# 4.net
KiCad netlist of a schematic drawn in Altium Designer
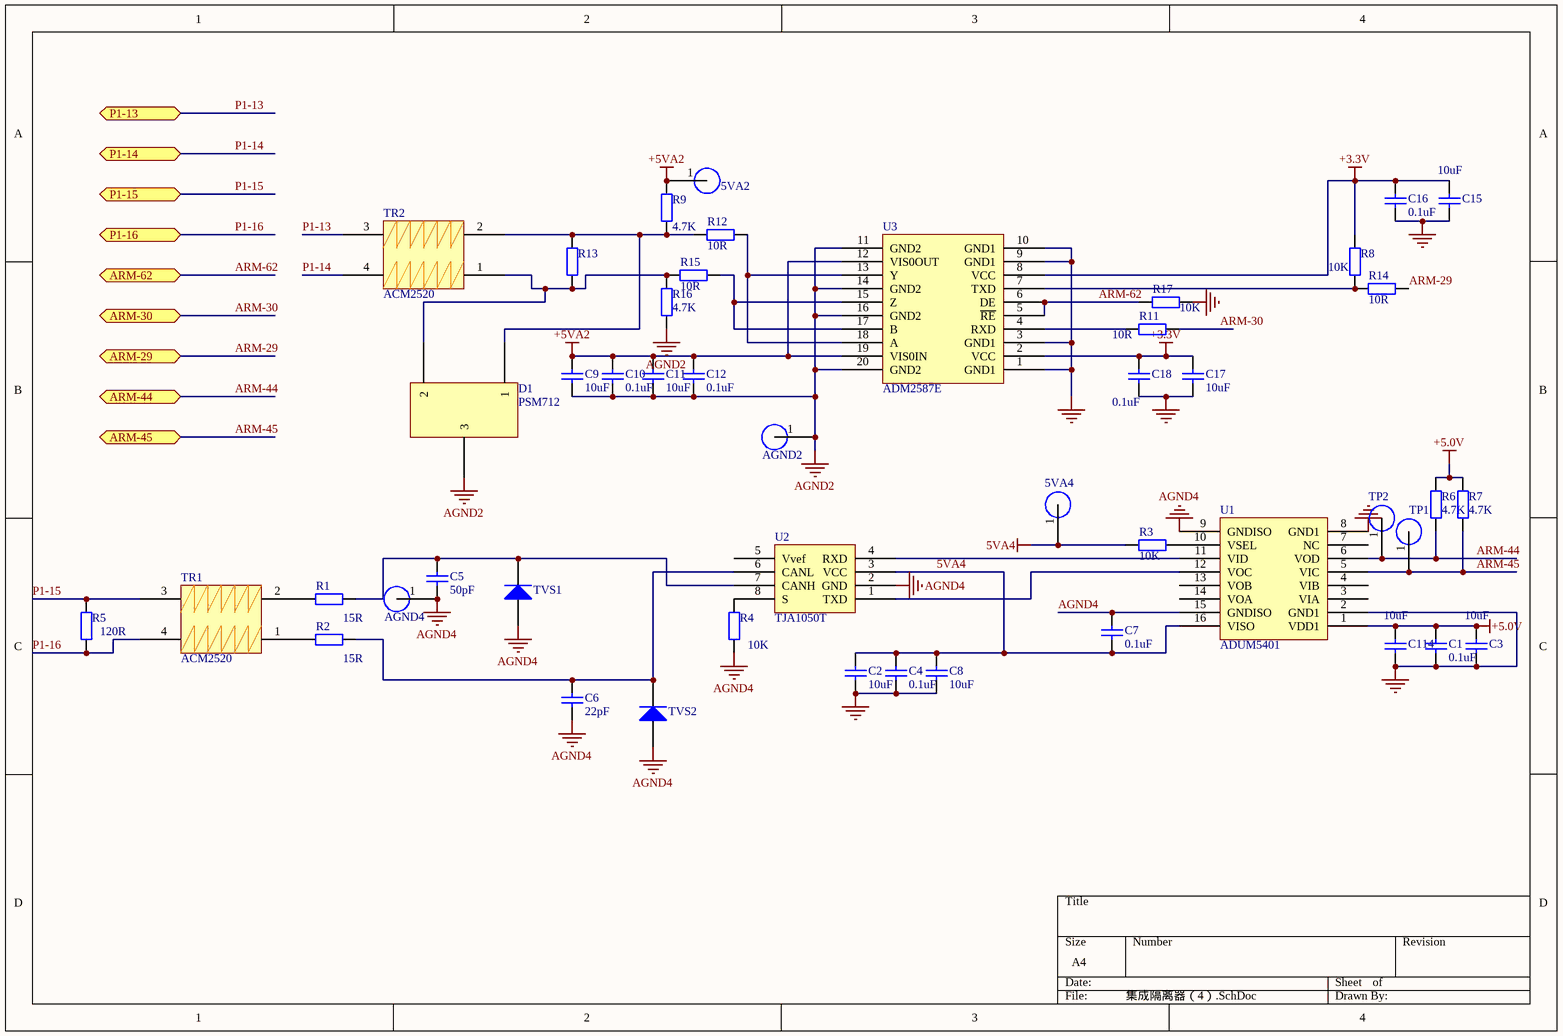
[diagram p0: 集成隔离器（4）.SchDoc]

(export (version "E")
  (design (tool "Eeschema 10.0.6"))
  (components
    (comp (ref "5VA2") (value "PIN") (footprint "圆形焊盘") (libsource (lib "圆孔") (part "Component_1")))
    (comp (ref "5VA4") (value "PIN") (footprint "圆形焊盘") (libsource (lib "") (part "Component_1_1")))
    (comp (ref "AGND2") (value "PIN") (footprint "圆形焊盘") (libsource (lib "圆孔") (part "Component_1")))
    (comp (ref "AGND4") (value "PIN") (footprint "圆形焊盘") (libsource (lib "圆孔") (part "Component_1")))
    (comp (ref "C1")
      (value "0.1uF")
      (footprint "采集板3.0增加1路模拟量2:C0805")
      (description "Capacitor")
      (fields (field (name "Comment") "Cap") (field (name "PUBLISHER") "Altium Limited"))
      (libsource (lib "Miscellaneous Devices") (part "Cap"))
    )
    (comp (ref "C2")
      (value "10uF")
      (footprint "C1206")
      (description "Capacitor")
      (fields (field (name "Comment") "Cap") (field (name "PUBLISHER") "Altium Limited"))
      (libsource (lib "Miscellaneous Devices") (part "Cap"))
    )
    (comp (ref "C3")
      (value "10uF")
      (footprint "C1206")
      (description "Capacitor")
      (fields (field (name "Comment") "Cap") (field (name "PUBLISHER") "Altium Limited"))
      (libsource (lib "Miscellaneous Devices") (part "Cap"))
    )
    (comp (ref "C4")
      (value "0.1uF")
      (footprint "采集板3.0增加1路模拟量2:C0805")
      (description "Capacitor")
      (fields (field (name "Comment") "Cap") (field (name "PUBLISHER") "Altium Limited"))
      (libsource (lib "Miscellaneous Devices") (part "Cap"))
    )
    (comp (ref "C5")
      (value "50pF")
      (footprint "C0805")
      (description "Capacitor")
      (fields (field (name "Comment") "Cap") (field (name "PUBLISHER") "Altium Limited"))
      (libsource (lib "Miscellaneous Devices") (part "Cap"))
    )
    (comp (ref "C6")
      (value "22pF")
      (footprint "采集板3.0增加1路模拟量2:C0805")
      (description "Capacitor")
      (fields (field (name "Comment") "Cap") (field (name "PUBLISHER") "Altium Limited"))
      (libsource (lib "Miscellaneous Devices") (part "Cap"))
    )
    (comp (ref "C7")
      (value "0.1uF")
      (footprint "采集板3.0增加1路模拟量2:C0805")
      (description "Capacitor")
      (fields (field (name "Comment") "Cap") (field (name "PUBLISHER") "Altium Limited"))
      (libsource (lib "Miscellaneous Devices") (part "Cap"))
    )
    (comp (ref "C8")
      (value "10uF")
      (footprint "C1206")
      (description "Capacitor")
      (fields (field (name "Comment") "Cap") (field (name "PUBLISHER") "Altium Limited"))
      (libsource (lib "Miscellaneous Devices") (part "Cap"))
    )
    (comp (ref "C9")
      (value "10uF")
      (footprint "C1206")
      (description "Capacitor")
      (fields (field (name "Comment") "Cap") (field (name "PUBLISHER") "Altium Limited"))
      (libsource (lib "Miscellaneous Devices") (part "Cap"))
    )
    (comp (ref "C10")
      (value "0.1uF")
      (footprint "采集板3.0增加1路模拟量2:C0805")
      (description "Capacitor")
      (fields (field (name "Comment") "Cap") (field (name "PUBLISHER") "Altium Limited"))
      (libsource (lib "Miscellaneous Devices") (part "Cap"))
    )
    (comp (ref "C11")
      (value "10uF")
      (footprint "C1206")
      (description "Capacitor")
      (fields (field (name "Comment") "Cap") (field (name "PUBLISHER") "Altium Limited"))
      (libsource (lib "Miscellaneous Devices") (part "Cap"))
    )
    (comp (ref "C12")
      (value "0.1uF")
      (footprint "采集板3.0增加1路模拟量2:C0805")
      (description "Capacitor")
      (fields (field (name "Comment") "Cap") (field (name "PUBLISHER") "Altium Limited"))
      (libsource (lib "Miscellaneous Devices") (part "Cap"))
    )
    (comp (ref "C15")
      (value "10uF")
      (footprint "C1206")
      (description "Capacitor")
      (fields (field (name "Comment") "Cap") (field (name "PUBLISHER") "Altium Limited"))
      (libsource (lib "Miscellaneous Devices") (part "Cap"))
    )
    (comp (ref "C16")
      (value "0.1uF")
      (footprint "采集板3.0增加1路模拟量2:C0805")
      (description "Capacitor")
      (fields (field (name "Comment") "Cap") (field (name "PUBLISHER") "Altium Limited"))
      (libsource (lib "Miscellaneous Devices") (part "Cap"))
    )
    (comp (ref "C17")
      (value "10uF")
      (footprint "C1206")
      (description "Capacitor")
      (fields (field (name "Comment") "Cap") (field (name "PUBLISHER") "Altium Limited"))
      (libsource (lib "Miscellaneous Devices") (part "Cap"))
    )
    (comp (ref "C18")
      (value "0.1uF")
      (footprint "采集板3.0增加1路模拟量2:C0805")
      (description "Capacitor")
      (fields (field (name "Comment") "Cap") (field (name "PUBLISHER") "Altium Limited"))
      (libsource (lib "Miscellaneous Devices") (part "Cap"))
    )
    (comp (ref "C114")
      (value "10uF")
      (footprint "C1206")
      (description "Capacitor")
      (fields (field (name "Comment") "Cap") (field (name "PUBLISHER") "Altium Limited"))
      (libsource (lib "Miscellaneous Devices") (part "Cap"))
    )
    (comp (ref "D1") (value "PSM712") (footprint "SOT23-3") (libsource (lib "标准电容阵列") (part "Component_1")))
    (comp (ref "R1")
      (value "15R")
      (footprint "采集板3.0增加1路模拟量2:R0805")
      (description "Resistor")
      (fields (field (name "Comment") "Res2") (field (name "PUBLISHER") "Altium Limited"))
      (libsource (lib "") (part "Res2_3"))
    )
    (comp (ref "R2")
      (value "15R")
      (footprint "采集板3.0增加1路模拟量2:R0805")
      (description "Resistor")
      (fields (field (name "Comment") "Res2") (field (name "PUBLISHER") "Altium Limited"))
      (libsource (lib "") (part "Res2_3"))
    )
    (comp (ref "R3")
      (value "10K")
      (footprint "采集板3.0增加1路模拟量2:R0805")
      (description "Resistor")
      (fields (field (name "Comment") "Res2") (field (name "PUBLISHER") "Altium Limited"))
      (libsource (lib "") (part "Res2_3"))
    )
    (comp (ref "R4")
      (value "10K")
      (footprint "采集板3.0增加1路模拟量2:R0805")
      (description "Resistor")
      (fields (field (name "Comment") "Res2") (field (name "PUBLISHER") "Altium Limited"))
      (libsource (lib "") (part "Res2_2"))
    )
    (comp (ref "R5")
      (value "120R")
      (footprint "R0805")
      (description "Resistor")
      (fields (field (name "Comment") "Res2") (field (name "PUBLISHER") "Altium Limited"))
      (libsource (lib "") (part "Res2_1"))
    )
    (comp (ref "R6")
      (value "4.7K")
      (footprint "采集板3.0增加1路模拟量2:R0805")
      (description "Resistor")
      (fields (field (name "Comment") "Res2") (field (name "PUBLISHER") "Altium Limited"))
      (libsource (lib "") (part "Res2_2"))
    )
    (comp (ref "R7")
      (value "4.7K")
      (footprint "采集板3.0增加1路模拟量2:R0805")
      (description "Resistor")
      (fields (field (name "Comment") "Res2") (field (name "PUBLISHER") "Altium Limited"))
      (libsource (lib "") (part "Res2_2"))
    )
    (comp (ref "R8")
      (value "10K")
      (footprint "采集板3.0增加1路模拟量2:R0805")
      (description "Resistor")
      (fields (field (name "Comment") "Res2") (field (name "PUBLISHER") "Altium Limited"))
      (libsource (lib "") (part "Res2_2"))
    )
    (comp (ref "R9")
      (value "4.7K")
      (footprint "采集板3.0增加1路模拟量2:R0805")
      (description "Resistor")
      (fields (field (name "Comment") "Res2") (field (name "PUBLISHER") "Altium Limited"))
      (libsource (lib "") (part "Res2_1"))
    )
    (comp (ref "R11")
      (value "10R")
      (footprint "采集板3.0增加1路模拟量2:R0805")
      (description "Resistor")
      (fields (field (name "Comment") "Res2") (field (name "PUBLISHER") "Altium Limited"))
      (libsource (lib "") (part "Res2_3"))
    )
    (comp (ref "R12")
      (value "10R")
      (footprint "采集板3.0增加1路模拟量2:R0805")
      (description "Resistor")
      (fields (field (name "Comment") "Res2") (field (name "PUBLISHER") "Altium Limited"))
      (libsource (lib "Miscellaneous Devices") (part "Res2"))
    )
    (comp (ref "R13")
      (value "Res2")
      (footprint "R0805")
      (description "Resistor")
      (fields (field (name "PUBLISHER") "Altium Limited"))
      (libsource (lib "") (part "Res2_1"))
    )
    (comp (ref "R14")
      (value "10R")
      (footprint "采集板3.0增加1路模拟量2:R0805")
      (description "Resistor")
      (fields (field (name "Comment") "Res2") (field (name "PUBLISHER") "Altium Limited"))
      (libsource (lib "") (part "Res2_3"))
    )
    (comp (ref "R15")
      (value "10R")
      (footprint "采集板3.0增加1路模拟量2:R0805")
      (description "Resistor")
      (fields (field (name "Comment") "Res2") (field (name "PUBLISHER") "Altium Limited"))
      (libsource (lib "Miscellaneous Devices") (part "Res2"))
    )
    (comp (ref "R16")
      (value "4.7K")
      (footprint "采集板3.0增加1路模拟量2:R0805")
      (description "Resistor")
      (fields (field (name "Comment") "Res2") (field (name "PUBLISHER") "Altium Limited"))
      (libsource (lib "") (part "Res2_2"))
    )
    (comp (ref "R17")
      (value "10K")
      (footprint "采集板3.0增加1路模拟量2:R0805")
      (description "Resistor")
      (fields (field (name "Comment") "Res2") (field (name "PUBLISHER") "Altium Limited"))
      (libsource (lib "Miscellaneous Devices") (part "Res2"))
    )
    (comp (ref "TP1") (value "PIN") (footprint "圆形焊盘") (libsource (lib "") (part "Component_1_1")))
    (comp (ref "TP2") (value "PIN") (footprint "圆形焊盘") (libsource (lib "") (part "Component_1_1")))
    (comp (ref "TR1") (value "ACM2520") (footprint "1008") (libsource (lib "ACM共模电感") (part "Component_1")))
    (comp (ref "TR2") (value "ACM2520") (footprint "1008") (libsource (lib "ACM共模电感") (part "Component_1")))
    (comp (ref "TVS1")
      (value "Diode 1N4007")
      (footprint "SMA")
      (description "1 Amp General Purpose Rectifier")
      (fields (field (name "PUBLISHER") "Altium Limited"))
      (libsource (lib "Miscellaneous Devices") (part "Diode 1N4007"))
    )
    (comp (ref "TVS2")
      (value "Diode 1N4007")
      (footprint "SMA")
      (description "1 Amp General Purpose Rectifier")
      (fields (field (name "PUBLISHER") "Altium Limited"))
      (libsource (lib "Miscellaneous Devices") (part "Diode 1N4007"))
    )
    (comp (ref "U1")
      (value "ADUM5401")
      (footprint "SOIC-16")
      (libsource (lib "ADUM5401") (part "Component_1"))
    )
    (comp (ref "U2") (value "TJA1050T") (footprint "SO-8") (libsource (lib "TJA1050T") (part "Component_1")))
    (comp (ref "U3")
      (value "ADM2587E")
      (footprint "SOIC-20")
      (libsource (lib "ADM2587E") (part "Component_1"))
    )
  )
  (nets
    (net (code "1") (name "+3.3V") (class "Default")
      (node (ref "C15") (pin "2") (pinfunction "2_2") (pintype "passive"))
      (node (ref "C16") (pin "1") (pinfunction "1_1") (pintype "passive"))
      (node (ref "C17") (pin "1") (pinfunction "1_1") (pintype "passive"))
      (node (ref "C18") (pin "2") (pinfunction "2_2") (pintype "passive"))
      (node (ref "R8") (pin "1") (pinfunction "1_1") (pintype "passive"))
      (node (ref "U3") (pin "2") (pinfunction "VCC_2") (pintype "passive"))
      (node (ref "U3") (pin "8") (pinfunction "VCC_8") (pintype "passive"))
    )
    (net (code "2") (name "+5.0V") (class "Default")
      (node (ref "C1") (pin "1") (pinfunction "1_1") (pintype "passive"))
      (node (ref "C114") (pin "2") (pinfunction "2_2") (pintype "passive"))
      (node (ref "C3") (pin "2") (pinfunction "2_2") (pintype "passive"))
      (node (ref "R6") (pin "1") (pinfunction "1_1") (pintype "passive"))
      (node (ref "R7") (pin "1") (pinfunction "1_1") (pintype "passive"))
      (node (ref "U1") (pin "1") (pinfunction "VDD1_1") (pintype "passive"))
    )
    (net (code "3") (name "+5VA2") (class "Default")
      (node (ref "5VA2") (pin "1") (pinfunction "1_1") (pintype "passive"))
      (node (ref "C10") (pin "1") (pinfunction "1_1") (pintype "passive"))
      (node (ref "C11") (pin "1") (pinfunction "1_1") (pintype "passive"))
      (node (ref "C12") (pin "2") (pinfunction "2_2") (pintype "passive"))
      (node (ref "C9") (pin "1") (pinfunction "1_1") (pintype "passive"))
      (node (ref "R9") (pin "2") (pinfunction "2_2") (pintype "passive"))
      (node (ref "U3") (pin "12") (pinfunction "VIS0OUT_12") (pintype "passive"))
      (node (ref "U3") (pin "19") (pinfunction "VIS0IN_19") (pintype "passive"))
    )
    (net (code "4") (name "/ARM-29") (class "Default")
      (node (ref "R14") (pin "1") (pinfunction "1_1") (pintype "passive"))
    )
    (net (code "5") (name "/ARM-30") (class "Default")
      (node (ref "R11") (pin "1") (pinfunction "1_1") (pintype "passive"))
    )
    (net (code "6") (name "/ARM-44") (class "Default")
      (node (ref "R6") (pin "2") (pinfunction "2_2") (pintype "passive"))
      (node (ref "TP2") (pin "1") (pinfunction "1_1") (pintype "passive"))
      (node (ref "U1") (pin "6") (pinfunction "VOD_6") (pintype "passive"))
    )
    (net (code "7") (name "/ARM-45") (class "Default")
      (node (ref "R7") (pin "2") (pinfunction "2_2") (pintype "passive"))
      (node (ref "TP1") (pin "1") (pinfunction "1_1") (pintype "passive"))
      (node (ref "U1") (pin "5") (pinfunction "VIC_5") (pintype "passive"))
    )
    (net (code "8") (name "/ARM-62") (class "Default")
      (node (ref "R17") (pin "1") (pinfunction "1_1") (pintype "passive"))
      (node (ref "U3") (pin "5") (pinfunction "~{RE}_5") (pintype "passive"))
      (node (ref "U3") (pin "6") (pinfunction "DE_6") (pintype "passive"))
    )
    (net (code "9") (name "/P1-13") (class "Default")
      (node (ref "TR2") (pin "3") (pinfunction "0_3") (pintype "passive"))
    )
    (net (code "10") (name "/P1-14") (class "Default")
      (node (ref "TR2") (pin "4") (pinfunction "4_4") (pintype "passive"))
    )
    (net (code "11") (name "/P1-15") (class "Default")
      (node (ref "R5") (pin "2") (pinfunction "2_2") (pintype "passive"))
      (node (ref "TR1") (pin "3") (pinfunction "0_3") (pintype "passive"))
    )
    (net (code "12") (name "/P1-16") (class "Default")
      (node (ref "R5") (pin "1") (pinfunction "1_1") (pintype "passive"))
      (node (ref "TR1") (pin "4") (pinfunction "4_4") (pintype "passive"))
    )
    (net (code "13") (name "5VA4") (class "Default")
      (node (ref "5VA4") (pin "1") (pinfunction "1_1") (pintype "passive"))
      (node (ref "C2") (pin "2") (pinfunction "2_2") (pintype "passive"))
      (node (ref "C4") (pin "1") (pinfunction "1_1") (pintype "passive"))
      (node (ref "C7") (pin "2") (pinfunction "2_2") (pintype "passive"))
      (node (ref "C8") (pin "2") (pinfunction "2_2") (pintype "passive"))
      (node (ref "R3") (pin "2") (pinfunction "2_2") (pintype "passive"))
      (node (ref "U1") (pin "16") (pinfunction "VISO_16") (pintype "passive"))
      (node (ref "U2") (pin "3") (pinfunction "VCC_3") (pintype "passive"))
    )
    (net (code "14") (name "AGND2") (class "Default")
      (node (ref "AGND2") (pin "1") (pinfunction "1_1") (pintype "passive"))
      (node (ref "C10") (pin "2") (pinfunction "2_2") (pintype "passive"))
      (node (ref "C11") (pin "2") (pinfunction "2_2") (pintype "passive"))
      (node (ref "C12") (pin "1") (pinfunction "1_1") (pintype "passive"))
      (node (ref "C9") (pin "2") (pinfunction "2_2") (pintype "passive"))
      (node (ref "D1") (pin "3") (pinfunction "3_3") (pintype "passive"))
      (node (ref "R16") (pin "2") (pinfunction "2_2") (pintype "passive"))
      (node (ref "U3") (pin "11") (pinfunction "GND2_11") (pintype "passive"))
      (node (ref "U3") (pin "14") (pinfunction "GND2_14") (pintype "passive"))
      (node (ref "U3") (pin "16") (pinfunction "GND2_16") (pintype "passive"))
      (node (ref "U3") (pin "20") (pinfunction "GND2_20") (pintype "passive"))
    )
    (net (code "15") (name "AGND4") (class "Default")
      (node (ref "AGND4") (pin "1") (pinfunction "1_1") (pintype "passive"))
      (node (ref "C2") (pin "1") (pinfunction "1_1") (pintype "passive"))
      (node (ref "C4") (pin "2") (pinfunction "2_2") (pintype "passive"))
      (node (ref "C5") (pin "1") (pinfunction "1_1") (pintype "passive"))
      (node (ref "C6") (pin "2") (pinfunction "2_2") (pintype "passive"))
      (node (ref "C7") (pin "1") (pinfunction "1_1") (pintype "passive"))
      (node (ref "C8") (pin "1") (pinfunction "1_1") (pintype "passive"))
      (node (ref "R4") (pin "2") (pinfunction "2_2") (pintype "passive"))
      (node (ref "TVS1") (pin "1") (pinfunction "A_1") (pintype "passive"))
      (node (ref "TVS2") (pin "1") (pinfunction "A_1") (pintype "passive"))
      (node (ref "U1") (pin "15") (pinfunction "GNDISO_15") (pintype "passive"))
      (node (ref "U1") (pin "9") (pinfunction "GNDISO_9") (pintype "passive"))
      (node (ref "U2") (pin "2") (pinfunction "GND_2") (pintype "passive"))
    )
    (net (code "16") (name "GND") (class "Default")
      (node (ref "C1") (pin "2") (pinfunction "2_2") (pintype "passive"))
      (node (ref "C114") (pin "1") (pinfunction "1_1") (pintype "passive"))
      (node (ref "C15") (pin "1") (pinfunction "1_1") (pintype "passive"))
      (node (ref "C16") (pin "2") (pinfunction "2_2") (pintype "passive"))
      (node (ref "C17") (pin "2") (pinfunction "2_2") (pintype "passive"))
      (node (ref "C18") (pin "1") (pinfunction "1_1") (pintype "passive"))
      (node (ref "C3") (pin "1") (pinfunction "1_1") (pintype "passive"))
      (node (ref "R17") (pin "2") (pinfunction "2_2") (pintype "passive"))
      (node (ref "U1") (pin "2") (pinfunction "GND1_2") (pintype "passive"))
      (node (ref "U1") (pin "8") (pinfunction "GND1_8") (pintype "passive"))
      (node (ref "U3") (pin "1") (pinfunction "GND1_1") (pintype "passive"))
      (node (ref "U3") (pin "10") (pinfunction "GND1_10") (pintype "passive"))
      (node (ref "U3") (pin "3") (pinfunction "GND1_3") (pintype "passive"))
      (node (ref "U3") (pin "9") (pinfunction "GND1_9") (pintype "passive"))
    )
    (net (code "17") (name "Net-(D1-Pad1)") (class "Default")
      (node (ref "D1") (pin "1") (pinfunction "1_1") (pintype "passive"))
      (node (ref "R12") (pin "1") (pinfunction "1_1") (pintype "passive"))
      (node (ref "R13") (pin "2") (pinfunction "2_2") (pintype "passive"))
      (node (ref "R9") (pin "1") (pinfunction "1_1") (pintype "passive"))
      (node (ref "TR2") (pin "2") (pinfunction "2_2") (pintype "passive"))
    )
    (net (code "18") (name "Net-(R1-Pad2)") (class "Default")
      (node (ref "R1") (pin "2") (pinfunction "2_2") (pintype "passive"))
      (node (ref "TR1") (pin "2") (pinfunction "2_2") (pintype "passive"))
    )
    (net (code "19") (name "Net-(TR1-3)") (class "Default")
      (node (ref "R2") (pin "2") (pinfunction "2_2") (pintype "passive"))
      (node (ref "TR1") (pin "1") (pinfunction "3_1") (pintype "passive"))
    )
    (net (code "20") (name "Net-(TR2-3)") (class "Default")
      (node (ref "D1") (pin "2") (pinfunction "2_2") (pintype "passive"))
      (node (ref "R13") (pin "1") (pinfunction "1_1") (pintype "passive"))
      (node (ref "R15") (pin "1") (pinfunction "1_1") (pintype "passive"))
      (node (ref "R16") (pin "1") (pinfunction "1_1") (pintype "passive"))
      (node (ref "TR2") (pin "1") (pinfunction "3_1") (pintype "passive"))
    )
    (net (code "21") (name "Net-(TVS1-K)") (class "Default")
      (node (ref "C5") (pin "2") (pinfunction "2_2") (pintype "passive"))
      (node (ref "R1") (pin "1") (pinfunction "1_1") (pintype "passive"))
      (node (ref "TVS1") (pin "2") (pinfunction "K_2") (pintype "passive"))
      (node (ref "U2") (pin "7") (pinfunction "CANH_7") (pintype "passive"))
    )
    (net (code "22") (name "Net-(TVS2-K)") (class "Default")
      (node (ref "C6") (pin "1") (pinfunction "1_1") (pintype "passive"))
      (node (ref "R2") (pin "1") (pinfunction "1_1") (pintype "passive"))
      (node (ref "TVS2") (pin "2") (pinfunction "K_2") (pintype "passive"))
      (node (ref "U2") (pin "6") (pinfunction "CANL_6") (pintype "passive"))
    )
    (net (code "23") (name "Net-(U1-VID)") (class "Default")
      (node (ref "U1") (pin "11") (pinfunction "VID_11") (pintype "passive"))
      (node (ref "U2") (pin "4") (pinfunction "RXD_4") (pintype "passive"))
    )
    (net (code "24") (name "Net-(U1-VOC)") (class "Default")
      (node (ref "U1") (pin "12") (pinfunction "VOC_12") (pintype "passive"))
      (node (ref "U2") (pin "1") (pinfunction "TXD_1") (pintype "passive"))
    )
    (net (code "25") (name "Net-(U1-VSEL)") (class "Default")
      (node (ref "R3") (pin "1") (pinfunction "1_1") (pintype "passive"))
      (node (ref "U1") (pin "10") (pinfunction "VSEL_10") (pintype "passive"))
    )
    (net (code "26") (name "Net-(U2-S)") (class "Default")
      (node (ref "R4") (pin "1") (pinfunction "1_1") (pintype "passive"))
      (node (ref "U2") (pin "8") (pinfunction "S_8") (pintype "passive"))
    )
    (net (code "27") (name "Net-(U3-A)") (class "Default")
      (node (ref "R12") (pin "2") (pinfunction "2_2") (pintype "passive"))
      (node (ref "U3") (pin "13") (pinfunction "Y_13") (pintype "passive"))
      (node (ref "U3") (pin "18") (pinfunction "A_18") (pintype "passive"))
    )
    (net (code "28") (name "Net-(U3-B)") (class "Default")
      (node (ref "R15") (pin "2") (pinfunction "2_2") (pintype "passive"))
      (node (ref "U3") (pin "15") (pinfunction "Z_15") (pintype "passive"))
      (node (ref "U3") (pin "17") (pinfunction "B_17") (pintype "passive"))
    )
    (net (code "29") (name "Net-(U3-RXD)") (class "Default")
      (node (ref "R11") (pin "2") (pinfunction "2_2") (pintype "passive"))
      (node (ref "U3") (pin "4") (pinfunction "RXD_4") (pintype "passive"))
    )
    (net (code "30") (name "Net-(U3-TXD)") (class "Default")
      (node (ref "R14") (pin "2") (pinfunction "2_2") (pintype "passive"))
      (node (ref "R8") (pin "2") (pinfunction "2_2") (pintype "passive"))
      (node (ref "U3") (pin "7") (pinfunction "TXD_7") (pintype "passive"))
    )
    (net (code "31") (name "unconnected-(U1-NC-Pad7)") (class "Default")
      (node (ref "U1") (pin "7") (pinfunction "NC_7") (pintype "passive"))
    )
    (net (code "32") (name "unconnected-(U1-VIA-Pad3)") (class "Default")
      (node (ref "U1") (pin "3") (pinfunction "VIA_3") (pintype "passive"))
    )
    (net (code "33") (name "unconnected-(U1-VIB-Pad4)") (class "Default")
      (node (ref "U1") (pin "4") (pinfunction "VIB_4") (pintype "passive"))
    )
    (net (code "34") (name "unconnected-(U1-VOA-Pad14)") (class "Default")
      (node (ref "U1") (pin "14") (pinfunction "VOA_14") (pintype "passive"))
    )
    (net (code "35") (name "unconnected-(U1-VOB-Pad13)") (class "Default")
      (node (ref "U1") (pin "13") (pinfunction "VOB_13") (pintype "passive"))
    )
    (net (code "36") (name "unconnected-(U2-Vvef-Pad5)") (class "Default")
      (node (ref "U2") (pin "5") (pinfunction "Vvef_5") (pintype "passive"))
    )
  )
)
